# PCB_LC_LPF-16-25.net
KiCad netlist of a schematic drawn in Altium Designer
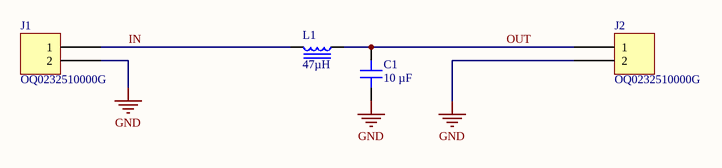
[diagram p0: PCB_LC_LPF-16-25.SchDoc]

(export (version "E")
  (design (tool "Eeschema 10.0.6"))
  (components
    (comp (ref "C1")
      (value "10 µF")
      (footprint "CAP 0603_1608")
      (description "CAP CER 10UF 10V X5R 0603")
      (fields
        (field (name "PART NUMBER") "MD0603BW106M100NHT-EM")
        (field (name "MANUFACTURER") "Knowles Novacap")
      )
      (libsource (lib "Celestial Altium Library - altium_library") (part "Capacitor"))
    )
    (comp (ref "J1")
      (value "OQ0232510000G")
      (footprint "FCI 06-381-2PIN")
      (description "TERM BLOCK HDR 2POS 90DEG 3.81MM")
      (fields (field (name "MANUFACTURER") "Amphenol Anytek"))
      (libsource (lib "Celestial Altium Library - altium_library") (part "2 Pin"))
    )
    (comp (ref "J2")
      (value "OQ0232510000G")
      (footprint "FCI 06-381-2PIN")
      (description "TERM BLOCK HDR 2POS 90DEG 3.81MM")
      (fields (field (name "MANUFACTURER") "Amphenol Anytek"))
      (libsource (lib "") (part "2 Pin_1"))
    )
    (comp (ref "L1")
      (value "47µH")
      (footprint "IND 0603_1608 RF WW")
      (description "INDUCTORPOWER LINE 0603 47H 20%")
      (fields (field (name "PART NUMBER") "L0603B470MPWFT") (field (name "MANUFACTURER") "KEMET"))
      (libsource (lib "Celestial Altium Library - altium_library") (part "Inductor"))
    )
  )
  (nets
    (net (code "1") (name "/IN") (class "Default")
      (node (ref "J1") (pin "1") (pinfunction "1_1") (pintype "passive"))
      (node (ref "L1") (pin "2") (pinfunction "2_2") (pintype "passive"))
    )
    (net (code "2") (name "/OUT") (class "Default")
      (node (ref "C1") (pin "2") (pinfunction "2_2") (pintype "passive"))
      (node (ref "J2") (pin "1") (pinfunction "1_1") (pintype "passive"))
      (node (ref "L1") (pin "1") (pinfunction "1_1") (pintype "passive"))
    )
    (net (code "3") (name "GND") (class "Default")
      (node (ref "C1") (pin "1") (pinfunction "1_1") (pintype "passive"))
      (node (ref "J1") (pin "2") (pinfunction "2_2") (pintype "passive"))
      (node (ref "J2") (pin "2") (pinfunction "2_2") (pintype "passive"))
    )
  )
)
